# 05-lnterface2.net
KiCad netlist of a schematic drawn in Altium Designer
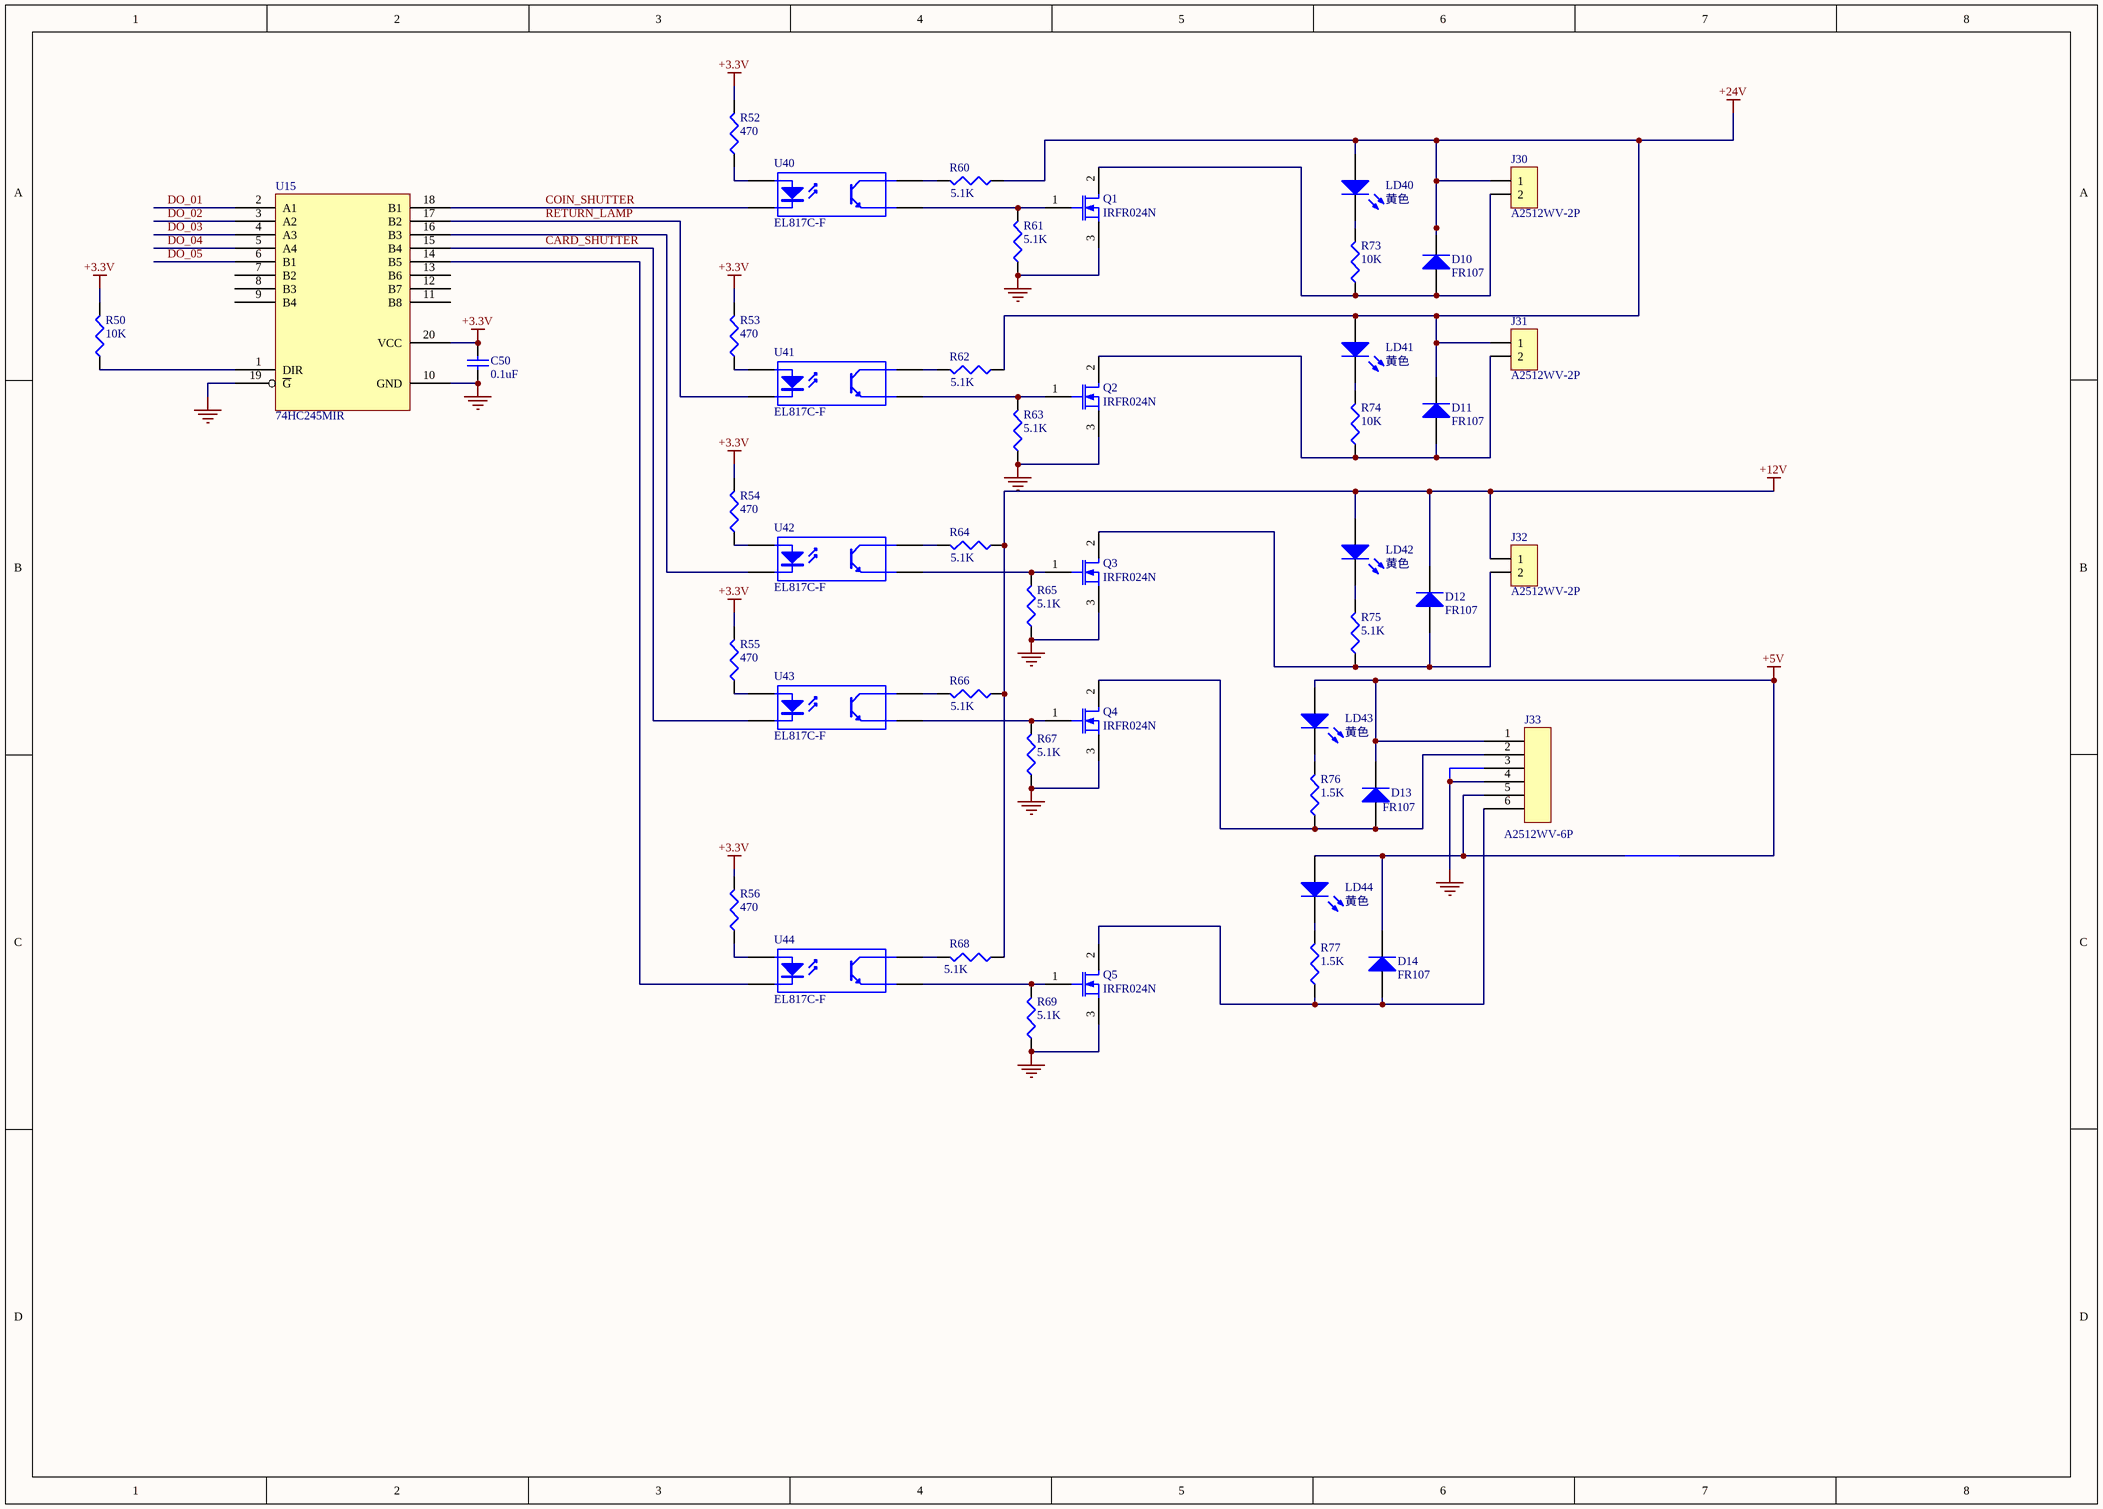
[diagram p0: 05-lnterface2.SchDoc]

(export (version "E")
  (design (tool "Eeschema 10.0.6"))
  (components
    (comp (ref "C50")
      (value "0.1uF")
      (footprint "C0805")
      (description "Capacitor")
      (fields (field (name "Comment") "Cap") (field (name "PUBLISHER") "Altium Limited"))
      (libsource (lib "Miscellaneous Devices") (part "Cap"))
    )
    (comp (ref "D10") (value "FR107") (footprint "FR107W") (libsource (lib "SCHLIB") (part "FR107")))
    (comp (ref "D11") (value "FR107") (footprint "FR107W") (libsource (lib "SCHLIB") (part "FR107")))
    (comp (ref "D12") (value "FR107") (footprint "FR107W") (libsource (lib "SCHLIB") (part "FR107")))
    (comp (ref "D13") (value "FR107") (footprint "FR107W") (libsource (lib "SCHLIB") (part "FR107")))
    (comp (ref "D14") (value "FR107") (footprint "FR107W") (libsource (lib "SCHLIB") (part "FR107")))
    (comp (ref "J30")
      (value "A2512WV-2P")
      (footprint "A2512WV-2P")
      (libsource (lib "SCHLIB") (part "A2512WV-2P"))
    )
    (comp (ref "J31")
      (value "A2512WV-2P")
      (footprint "A2512WV-2P")
      (libsource (lib "SCHLIB") (part "A2512WV-2P"))
    )
    (comp (ref "J32")
      (value "A2512WV-2P")
      (footprint "A2512WV-2P")
      (libsource (lib "SCHLIB") (part "A2512WV-2P"))
    )
    (comp (ref "J33")
      (value "A2512WV-6P")
      (footprint "A2512WV-6P")
      (libsource (lib "SCHLIB") (part "A2512WV-6P"))
    )
    (comp (ref "LD40")
      (value "黄色")
      (footprint "LED0805")
      (description "Typical INFRARED GaAs LED")
      (fields (field (name "PUBLISHER") "Altium Limited"))
      (libsource (lib "Miscellaneous Devices") (part "LED0"))
    )
    (comp (ref "LD41")
      (value "黄色")
      (footprint "LED0805")
      (description "Typical INFRARED GaAs LED")
      (fields (field (name "PUBLISHER") "Altium Limited"))
      (libsource (lib "Miscellaneous Devices") (part "LED0"))
    )
    (comp (ref "LD42")
      (value "黄色")
      (footprint "LED0805")
      (description "Typical INFRARED GaAs LED")
      (fields (field (name "PUBLISHER") "Altium Limited"))
      (libsource (lib "Miscellaneous Devices") (part "LED0"))
    )
    (comp (ref "LD43")
      (value "黄色")
      (footprint "LED0805")
      (description "Typical INFRARED GaAs LED")
      (fields (field (name "PUBLISHER") "Altium Limited"))
      (libsource (lib "Miscellaneous Devices") (part "LED0"))
    )
    (comp (ref "LD44")
      (value "黄色")
      (footprint "LED0805")
      (description "Typical INFRARED GaAs LED")
      (fields (field (name "PUBLISHER") "Altium Limited"))
      (libsource (lib "Miscellaneous Devices") (part "LED0"))
    )
    (comp (ref "Q1") (value "IRFR024N") (footprint "TO-252AA") (libsource (lib "SCHLIB") (part "IRFR024N")))
    (comp (ref "Q2") (value "IRFR024N") (footprint "TO-252AA") (libsource (lib "SCHLIB") (part "IRFR024N")))
    (comp (ref "Q3") (value "IRFR024N") (footprint "TO-252AA") (libsource (lib "SCHLIB") (part "IRFR024N")))
    (comp (ref "Q4") (value "IRFR024N") (footprint "TO-252AA") (libsource (lib "SCHLIB") (part "IRFR024N")))
    (comp (ref "Q5") (value "IRFR024N") (footprint "TO-252AA") (libsource (lib "SCHLIB") (part "IRFR024N")))
    (comp (ref "R50")
      (value "10K")
      (footprint "R0805")
      (description "Resistor")
      (fields (field (name "Comment") "Res3") (field (name "PUBLISHER") "Altium Limited"))
      (libsource (lib "Miscellaneous Devices") (part "Res3"))
    )
    (comp (ref "R52")
      (value "470")
      (footprint "R0805")
      (description "Resistor")
      (fields (field (name "Comment") "Res3") (field (name "PUBLISHER") "Altium Limited"))
      (libsource (lib "Miscellaneous Devices") (part "Res3"))
    )
    (comp (ref "R53")
      (value "470")
      (footprint "R0805")
      (description "Resistor")
      (fields (field (name "Comment") "Res3") (field (name "PUBLISHER") "Altium Limited"))
      (libsource (lib "Miscellaneous Devices") (part "Res3"))
    )
    (comp (ref "R54")
      (value "470")
      (footprint "R0805")
      (description "Resistor")
      (fields (field (name "Comment") "Res3") (field (name "PUBLISHER") "Altium Limited"))
      (libsource (lib "Miscellaneous Devices") (part "Res3"))
    )
    (comp (ref "R55")
      (value "470")
      (footprint "R0805")
      (description "Resistor")
      (fields (field (name "Comment") "Res3") (field (name "PUBLISHER") "Altium Limited"))
      (libsource (lib "Miscellaneous Devices") (part "Res3"))
    )
    (comp (ref "R56")
      (value "470")
      (footprint "R0805")
      (description "Resistor")
      (fields (field (name "Comment") "Res3") (field (name "PUBLISHER") "Altium Limited"))
      (libsource (lib "Miscellaneous Devices") (part "Res3"))
    )
    (comp (ref "R60")
      (value "5.1K")
      (footprint "R0805")
      (description "Resistor")
      (fields (field (name "Comment") "Res3") (field (name "PUBLISHER") "Altium Limited"))
      (libsource (lib "Miscellaneous Devices") (part "Res3"))
    )
    (comp (ref "R61")
      (value "5.1K")
      (footprint "R0805")
      (description "Resistor")
      (fields (field (name "Comment") "Res3") (field (name "PUBLISHER") "Altium Limited"))
      (libsource (lib "Miscellaneous Devices") (part "Res3"))
    )
    (comp (ref "R62")
      (value "5.1K")
      (footprint "R0805")
      (description "Resistor")
      (fields (field (name "Comment") "Res3") (field (name "PUBLISHER") "Altium Limited"))
      (libsource (lib "Miscellaneous Devices") (part "Res3"))
    )
    (comp (ref "R63")
      (value "5.1K")
      (footprint "R0805")
      (description "Resistor")
      (fields (field (name "Comment") "Res3") (field (name "PUBLISHER") "Altium Limited"))
      (libsource (lib "Miscellaneous Devices") (part "Res3"))
    )
    (comp (ref "R64")
      (value "5.1K")
      (footprint "R0805")
      (description "Resistor")
      (fields (field (name "Comment") "Res3") (field (name "PUBLISHER") "Altium Limited"))
      (libsource (lib "Miscellaneous Devices") (part "Res3"))
    )
    (comp (ref "R65")
      (value "5.1K")
      (footprint "R0805")
      (description "Resistor")
      (fields (field (name "Comment") "Res3") (field (name "PUBLISHER") "Altium Limited"))
      (libsource (lib "Miscellaneous Devices") (part "Res3"))
    )
    (comp (ref "R66")
      (value "5.1K")
      (footprint "R0805")
      (description "Resistor")
      (fields (field (name "Comment") "Res3") (field (name "PUBLISHER") "Altium Limited"))
      (libsource (lib "Miscellaneous Devices") (part "Res3"))
    )
    (comp (ref "R67")
      (value "5.1K")
      (footprint "R0805")
      (description "Resistor")
      (fields (field (name "Comment") "Res3") (field (name "PUBLISHER") "Altium Limited"))
      (libsource (lib "Miscellaneous Devices") (part "Res3"))
    )
    (comp (ref "R68")
      (value "5.1K")
      (footprint "R0805")
      (description "Resistor")
      (fields (field (name "Comment") "Res3") (field (name "PUBLISHER") "Altium Limited"))
      (libsource (lib "Miscellaneous Devices") (part "Res3"))
    )
    (comp (ref "R69")
      (value "5.1K")
      (footprint "R0805")
      (description "Resistor")
      (fields (field (name "Comment") "Res3") (field (name "PUBLISHER") "Altium Limited"))
      (libsource (lib "Miscellaneous Devices") (part "Res3"))
    )
    (comp (ref "R73")
      (value "10K")
      (footprint "R0805")
      (description "Resistor")
      (fields (field (name "Comment") "Res3") (field (name "PUBLISHER") "Altium Limited"))
      (libsource (lib "Miscellaneous Devices") (part "Res3"))
    )
    (comp (ref "R74")
      (value "10K")
      (footprint "R0805")
      (description "Resistor")
      (fields (field (name "Comment") "Res3") (field (name "PUBLISHER") "Altium Limited"))
      (libsource (lib "Miscellaneous Devices") (part "Res3"))
    )
    (comp (ref "R75")
      (value "5.1K")
      (footprint "R0805")
      (description "Resistor")
      (fields (field (name "Comment") "Res3") (field (name "PUBLISHER") "Altium Limited"))
      (libsource (lib "Miscellaneous Devices") (part "Res3"))
    )
    (comp (ref "R76")
      (value "1.5K")
      (footprint "R0805")
      (description "Resistor")
      (fields (field (name "Comment") "Res3") (field (name "PUBLISHER") "Altium Limited"))
      (libsource (lib "Miscellaneous Devices") (part "Res3"))
    )
    (comp (ref "R77")
      (value "1.5K")
      (footprint "R0805")
      (description "Resistor")
      (fields (field (name "Comment") "Res3") (field (name "PUBLISHER") "Altium Limited"))
      (libsource (lib "Miscellaneous Devices") (part "Res3"))
    )
    (comp (ref "U15")
      (value "74HC245MIR")
      (footprint "SSOP-20")
      (libsource (lib "SCHLIB") (part "74HC245MIR"))
    )
    (comp (ref "U40")
      (value "EL817C-F")
      (footprint "EL817-S")
      (description "Optoisolator")
      (fields (field (name "PUBLISHER") "Altium Limited"))
      (libsource (lib "Miscellaneous Devices") (part "Optoisolator1"))
    )
    (comp (ref "U41")
      (value "EL817C-F")
      (footprint "EL817-S")
      (description "Optoisolator")
      (fields (field (name "PUBLISHER") "Altium Limited"))
      (libsource (lib "Miscellaneous Devices") (part "Optoisolator1"))
    )
    (comp (ref "U42")
      (value "EL817C-F")
      (footprint "EL817-S")
      (description "Optoisolator")
      (fields (field (name "PUBLISHER") "Altium Limited"))
      (libsource (lib "Miscellaneous Devices") (part "Optoisolator1"))
    )
    (comp (ref "U43")
      (value "EL817C-F")
      (footprint "EL817-S")
      (description "Optoisolator")
      (fields (field (name "PUBLISHER") "Altium Limited"))
      (libsource (lib "Miscellaneous Devices") (part "Optoisolator1"))
    )
    (comp (ref "U44")
      (value "EL817C-F")
      (footprint "EL817-S")
      (description "Optoisolator")
      (fields (field (name "PUBLISHER") "Altium Limited"))
      (libsource (lib "Miscellaneous Devices") (part "Optoisolator1"))
    )
  )
  (nets
    (net (code "1") (name "+3.3V") (class "Default")
      (node (ref "C50") (pin "2") (pinfunction "2_2") (pintype "passive"))
      (node (ref "R50") (pin "2") (pinfunction "2_2") (pintype "passive"))
      (node (ref "R52") (pin "2") (pinfunction "2_2") (pintype "passive"))
      (node (ref "R53") (pin "2") (pinfunction "2_2") (pintype "passive"))
      (node (ref "R54") (pin "2") (pinfunction "2_2") (pintype "passive"))
      (node (ref "R55") (pin "2") (pinfunction "2_2") (pintype "passive"))
      (node (ref "R56") (pin "2") (pinfunction "2_2") (pintype "passive"))
      (node (ref "U15") (pin "20") (pinfunction "VCC_20") (pintype "passive"))
    )
    (net (code "2") (name "+5V") (class "Default")
      (node (ref "D13") (pin "2") (pinfunction "K_2") (pintype "passive"))
      (node (ref "D14") (pin "2") (pinfunction "K_2") (pintype "passive"))
      (node (ref "J33") (pin "1") (pinfunction "1_1") (pintype "passive"))
      (node (ref "J33") (pin "5") (pinfunction "5_5") (pintype "passive"))
      (node (ref "LD43") (pin "1") (pinfunction "A_1") (pintype "passive"))
      (node (ref "LD44") (pin "1") (pinfunction "A_1") (pintype "passive"))
    )
    (net (code "3") (name "+12V") (class "Default")
      (node (ref "D12") (pin "2") (pinfunction "K_2") (pintype "passive"))
      (node (ref "J32") (pin "1") (pinfunction "1_1") (pintype "passive"))
      (node (ref "LD42") (pin "1") (pinfunction "A_1") (pintype "passive"))
      (node (ref "R64") (pin "1") (pinfunction "1_1") (pintype "passive"))
      (node (ref "R66") (pin "1") (pinfunction "1_1") (pintype "passive"))
      (node (ref "R68") (pin "1") (pinfunction "1_1") (pintype "passive"))
    )
    (net (code "4") (name "+24V") (class "Default")
      (node (ref "D10") (pin "2") (pinfunction "K_2") (pintype "passive"))
      (node (ref "D11") (pin "2") (pinfunction "K_2") (pintype "passive"))
      (node (ref "J30") (pin "1") (pinfunction "1_1") (pintype "passive"))
      (node (ref "J31") (pin "1") (pinfunction "1_1") (pintype "passive"))
      (node (ref "LD40") (pin "1") (pinfunction "A_1") (pintype "passive"))
      (node (ref "LD41") (pin "1") (pinfunction "A_1") (pintype "passive"))
      (node (ref "R60") (pin "1") (pinfunction "1_1") (pintype "passive"))
      (node (ref "R62") (pin "1") (pinfunction "1_1") (pintype "passive"))
    )
    (net (code "5") (name "/CARD_SHUTTER") (class "Default")
      (node (ref "U15") (pin "15") (pinfunction "B4_15") (pintype "passive"))
      (node (ref "U43") (pin "2") (pinfunction "K_2") (pintype "passive"))
    )
    (net (code "6") (name "/COIN_SHUTTER") (class "Default")
      (node (ref "U15") (pin "18") (pinfunction "B1_18") (pintype "passive"))
      (node (ref "U40") (pin "2") (pinfunction "K_2") (pintype "passive"))
    )
    (net (code "7") (name "/DO_01") (class "Default")
      (node (ref "U15") (pin "2") (pinfunction "A1_2") (pintype "passive"))
    )
    (net (code "8") (name "/DO_02") (class "Default")
      (node (ref "U15") (pin "3") (pinfunction "A2_3") (pintype "passive"))
    )
    (net (code "9") (name "/DO_03") (class "Default")
      (node (ref "U15") (pin "4") (pinfunction "A3_4") (pintype "passive"))
    )
    (net (code "10") (name "/DO_04") (class "Default")
      (node (ref "U15") (pin "5") (pinfunction "A4_5") (pintype "passive"))
    )
    (net (code "11") (name "/DO_05") (class "Default")
      (node (ref "U15") (pin "6") (pinfunction "B1_6") (pintype "passive"))
    )
    (net (code "12") (name "/RETURN_LAMP") (class "Default")
      (node (ref "U15") (pin "17") (pinfunction "B2_17") (pintype "passive"))
      (node (ref "U41") (pin "2") (pinfunction "K_2") (pintype "passive"))
    )
    (net (code "13") (name "GND") (class "Default")
      (node (ref "C50") (pin "1") (pinfunction "1_1") (pintype "passive"))
      (node (ref "J33") (pin "3") (pinfunction "3_3") (pintype "passive"))
      (node (ref "J33") (pin "4") (pinfunction "4_4") (pintype "passive"))
      (node (ref "Q1") (pin "3") (pinfunction "3_3") (pintype "passive"))
      (node (ref "Q2") (pin "3") (pinfunction "3_3") (pintype "passive"))
      (node (ref "Q3") (pin "3") (pinfunction "3_3") (pintype "passive"))
      (node (ref "Q4") (pin "3") (pinfunction "3_3") (pintype "passive"))
      (node (ref "Q5") (pin "3") (pinfunction "3_3") (pintype "passive"))
      (node (ref "R61") (pin "1") (pinfunction "1_1") (pintype "passive"))
      (node (ref "R63") (pin "1") (pinfunction "1_1") (pintype "passive"))
      (node (ref "R65") (pin "1") (pinfunction "1_1") (pintype "passive"))
      (node (ref "R67") (pin "1") (pinfunction "1_1") (pintype "passive"))
      (node (ref "R69") (pin "1") (pinfunction "1_1") (pintype "passive"))
      (node (ref "U15") (pin "10") (pinfunction "GND_10") (pintype "passive"))
      (node (ref "U15") (pin "19") (pinfunction "~{G}_19") (pintype "passive"))
    )
    (net (code "14") (name "Net-(D10-A)") (class "Default")
      (node (ref "D10") (pin "1") (pinfunction "A_1") (pintype "passive"))
      (node (ref "J30") (pin "2") (pinfunction "2_2") (pintype "passive"))
      (node (ref "Q1") (pin "2") (pinfunction "2_2") (pintype "passive"))
      (node (ref "R73") (pin "1") (pinfunction "1_1") (pintype "passive"))
    )
    (net (code "15") (name "Net-(D11-A)") (class "Default")
      (node (ref "D11") (pin "1") (pinfunction "A_1") (pintype "passive"))
      (node (ref "J31") (pin "2") (pinfunction "2_2") (pintype "passive"))
      (node (ref "Q2") (pin "2") (pinfunction "2_2") (pintype "passive"))
      (node (ref "R74") (pin "1") (pinfunction "1_1") (pintype "passive"))
    )
    (net (code "16") (name "Net-(D12-A)") (class "Default")
      (node (ref "D12") (pin "1") (pinfunction "A_1") (pintype "passive"))
      (node (ref "J32") (pin "2") (pinfunction "2_2") (pintype "passive"))
      (node (ref "Q3") (pin "2") (pinfunction "2_2") (pintype "passive"))
      (node (ref "R75") (pin "1") (pinfunction "1_1") (pintype "passive"))
    )
    (net (code "17") (name "Net-(D13-A)") (class "Default")
      (node (ref "D13") (pin "1") (pinfunction "A_1") (pintype "passive"))
      (node (ref "J33") (pin "2") (pinfunction "2_2") (pintype "passive"))
      (node (ref "Q4") (pin "2") (pinfunction "2_2") (pintype "passive"))
      (node (ref "R76") (pin "1") (pinfunction "1_1") (pintype "passive"))
    )
    (net (code "18") (name "Net-(D14-A)") (class "Default")
      (node (ref "D14") (pin "1") (pinfunction "A_1") (pintype "passive"))
      (node (ref "J33") (pin "6") (pinfunction "6_6") (pintype "passive"))
      (node (ref "Q5") (pin "2") (pinfunction "2_2") (pintype "passive"))
      (node (ref "R77") (pin "1") (pinfunction "1_1") (pintype "passive"))
    )
    (net (code "19") (name "Net-(LD40-K)") (class "Default")
      (node (ref "LD40") (pin "2") (pinfunction "K_2") (pintype "passive"))
      (node (ref "R73") (pin "2") (pinfunction "2_2") (pintype "passive"))
    )
    (net (code "20") (name "Net-(LD41-K)") (class "Default")
      (node (ref "LD41") (pin "2") (pinfunction "K_2") (pintype "passive"))
      (node (ref "R74") (pin "2") (pinfunction "2_2") (pintype "passive"))
    )
    (net (code "21") (name "Net-(LD42-K)") (class "Default")
      (node (ref "LD42") (pin "2") (pinfunction "K_2") (pintype "passive"))
      (node (ref "R75") (pin "2") (pinfunction "2_2") (pintype "passive"))
    )
    (net (code "22") (name "Net-(LD43-K)") (class "Default")
      (node (ref "LD43") (pin "2") (pinfunction "K_2") (pintype "passive"))
      (node (ref "R76") (pin "2") (pinfunction "2_2") (pintype "passive"))
    )
    (net (code "23") (name "Net-(LD44-K)") (class "Default")
      (node (ref "LD44") (pin "2") (pinfunction "K_2") (pintype "passive"))
      (node (ref "R77") (pin "2") (pinfunction "2_2") (pintype "passive"))
    )
    (net (code "24") (name "Net-(U15-B5)") (class "Default")
      (node (ref "U15") (pin "14") (pinfunction "B5_14") (pintype "passive"))
      (node (ref "U44") (pin "2") (pinfunction "K_2") (pintype "passive"))
    )
    (net (code "25") (name "Net-(U15-DIR)") (class "Default")
      (node (ref "R50") (pin "1") (pinfunction "1_1") (pintype "passive"))
      (node (ref "U15") (pin "1") (pinfunction "DIR_1") (pintype "passive"))
    )
    (net (code "26") (name "Net-(U40-A)") (class "Default")
      (node (ref "R52") (pin "1") (pinfunction "1_1") (pintype "passive"))
      (node (ref "U40") (pin "1") (pinfunction "A_1") (pintype "passive"))
    )
    (net (code "27") (name "Net-(U40-C)") (class "Default")
      (node (ref "R60") (pin "2") (pinfunction "2_2") (pintype "passive"))
      (node (ref "U40") (pin "3") (pinfunction "C_3") (pintype "passive"))
    )
    (net (code "28") (name "Net-(U40-E)") (class "Default")
      (node (ref "Q1") (pin "1") (pinfunction "1_1") (pintype "passive"))
      (node (ref "R61") (pin "2") (pinfunction "2_2") (pintype "passive"))
      (node (ref "U40") (pin "4") (pinfunction "E_4") (pintype "passive"))
    )
    (net (code "29") (name "Net-(U41-A)") (class "Default")
      (node (ref "R53") (pin "1") (pinfunction "1_1") (pintype "passive"))
      (node (ref "U41") (pin "1") (pinfunction "A_1") (pintype "passive"))
    )
    (net (code "30") (name "Net-(U41-C)") (class "Default")
      (node (ref "R62") (pin "2") (pinfunction "2_2") (pintype "passive"))
      (node (ref "U41") (pin "3") (pinfunction "C_3") (pintype "passive"))
    )
    (net (code "31") (name "Net-(U41-E)") (class "Default")
      (node (ref "Q2") (pin "1") (pinfunction "1_1") (pintype "passive"))
      (node (ref "R63") (pin "2") (pinfunction "2_2") (pintype "passive"))
      (node (ref "U41") (pin "4") (pinfunction "E_4") (pintype "passive"))
    )
    (net (code "32") (name "Net-(U42-A)") (class "Default")
      (node (ref "R54") (pin "1") (pinfunction "1_1") (pintype "passive"))
      (node (ref "U42") (pin "1") (pinfunction "A_1") (pintype "passive"))
    )
    (net (code "33") (name "Net-(U42-C)") (class "Default")
      (node (ref "R64") (pin "2") (pinfunction "2_2") (pintype "passive"))
      (node (ref "U42") (pin "3") (pinfunction "C_3") (pintype "passive"))
    )
    (net (code "34") (name "Net-(U42-E)") (class "Default")
      (node (ref "Q3") (pin "1") (pinfunction "1_1") (pintype "passive"))
      (node (ref "R65") (pin "2") (pinfunction "2_2") (pintype "passive"))
      (node (ref "U42") (pin "4") (pinfunction "E_4") (pintype "passive"))
    )
    (net (code "35") (name "Net-(U42-K)") (class "Default")
      (node (ref "U15") (pin "16") (pinfunction "B3_16") (pintype "passive"))
      (node (ref "U42") (pin "2") (pinfunction "K_2") (pintype "passive"))
    )
    (net (code "36") (name "Net-(U43-A)") (class "Default")
      (node (ref "R55") (pin "1") (pinfunction "1_1") (pintype "passive"))
      (node (ref "U43") (pin "1") (pinfunction "A_1") (pintype "passive"))
    )
    (net (code "37") (name "Net-(U43-C)") (class "Default")
      (node (ref "R66") (pin "2") (pinfunction "2_2") (pintype "passive"))
      (node (ref "U43") (pin "3") (pinfunction "C_3") (pintype "passive"))
    )
    (net (code "38") (name "Net-(U43-E)") (class "Default")
      (node (ref "Q4") (pin "1") (pinfunction "1_1") (pintype "passive"))
      (node (ref "R67") (pin "2") (pinfunction "2_2") (pintype "passive"))
      (node (ref "U43") (pin "4") (pinfunction "E_4") (pintype "passive"))
    )
    (net (code "39") (name "Net-(U44-A)") (class "Default")
      (node (ref "R56") (pin "1") (pinfunction "1_1") (pintype "passive"))
      (node (ref "U44") (pin "1") (pinfunction "A_1") (pintype "passive"))
    )
    (net (code "40") (name "Net-(U44-C)") (class "Default")
      (node (ref "R68") (pin "2") (pinfunction "2_2") (pintype "passive"))
      (node (ref "U44") (pin "3") (pinfunction "C_3") (pintype "passive"))
    )
    (net (code "41") (name "Net-(U44-E)") (class "Default")
      (node (ref "Q5") (pin "1") (pinfunction "1_1") (pintype "passive"))
      (node (ref "R69") (pin "2") (pinfunction "2_2") (pintype "passive"))
      (node (ref "U44") (pin "4") (pinfunction "E_4") (pintype "passive"))
    )
    (net (code "42") (name "unconnected-(U15-B2-Pad7)") (class "Default")
      (node (ref "U15") (pin "7") (pinfunction "B2_7") (pintype "passive"))
    )
    (net (code "43") (name "unconnected-(U15-B3-Pad8)") (class "Default")
      (node (ref "U15") (pin "8") (pinfunction "B3_8") (pintype "passive"))
    )
    (net (code "44") (name "unconnected-(U15-B4-Pad9)") (class "Default")
      (node (ref "U15") (pin "9") (pinfunction "B4_9") (pintype "passive"))
    )
    (net (code "45") (name "unconnected-(U15-B6-Pad13)") (class "Default")
      (node (ref "U15") (pin "13") (pinfunction "B6_13") (pintype "passive"))
    )
    (net (code "46") (name "unconnected-(U15-B7-Pad12)") (class "Default")
      (node (ref "U15") (pin "12") (pinfunction "B7_12") (pintype "passive"))
    )
    (net (code "47") (name "unconnected-(U15-B8-Pad11)") (class "Default")
      (node (ref "U15") (pin "11") (pinfunction "B8_11") (pintype "passive"))
    )
  )
)
